# MCU.net
KiCad netlist of a schematic drawn in Altium Designer
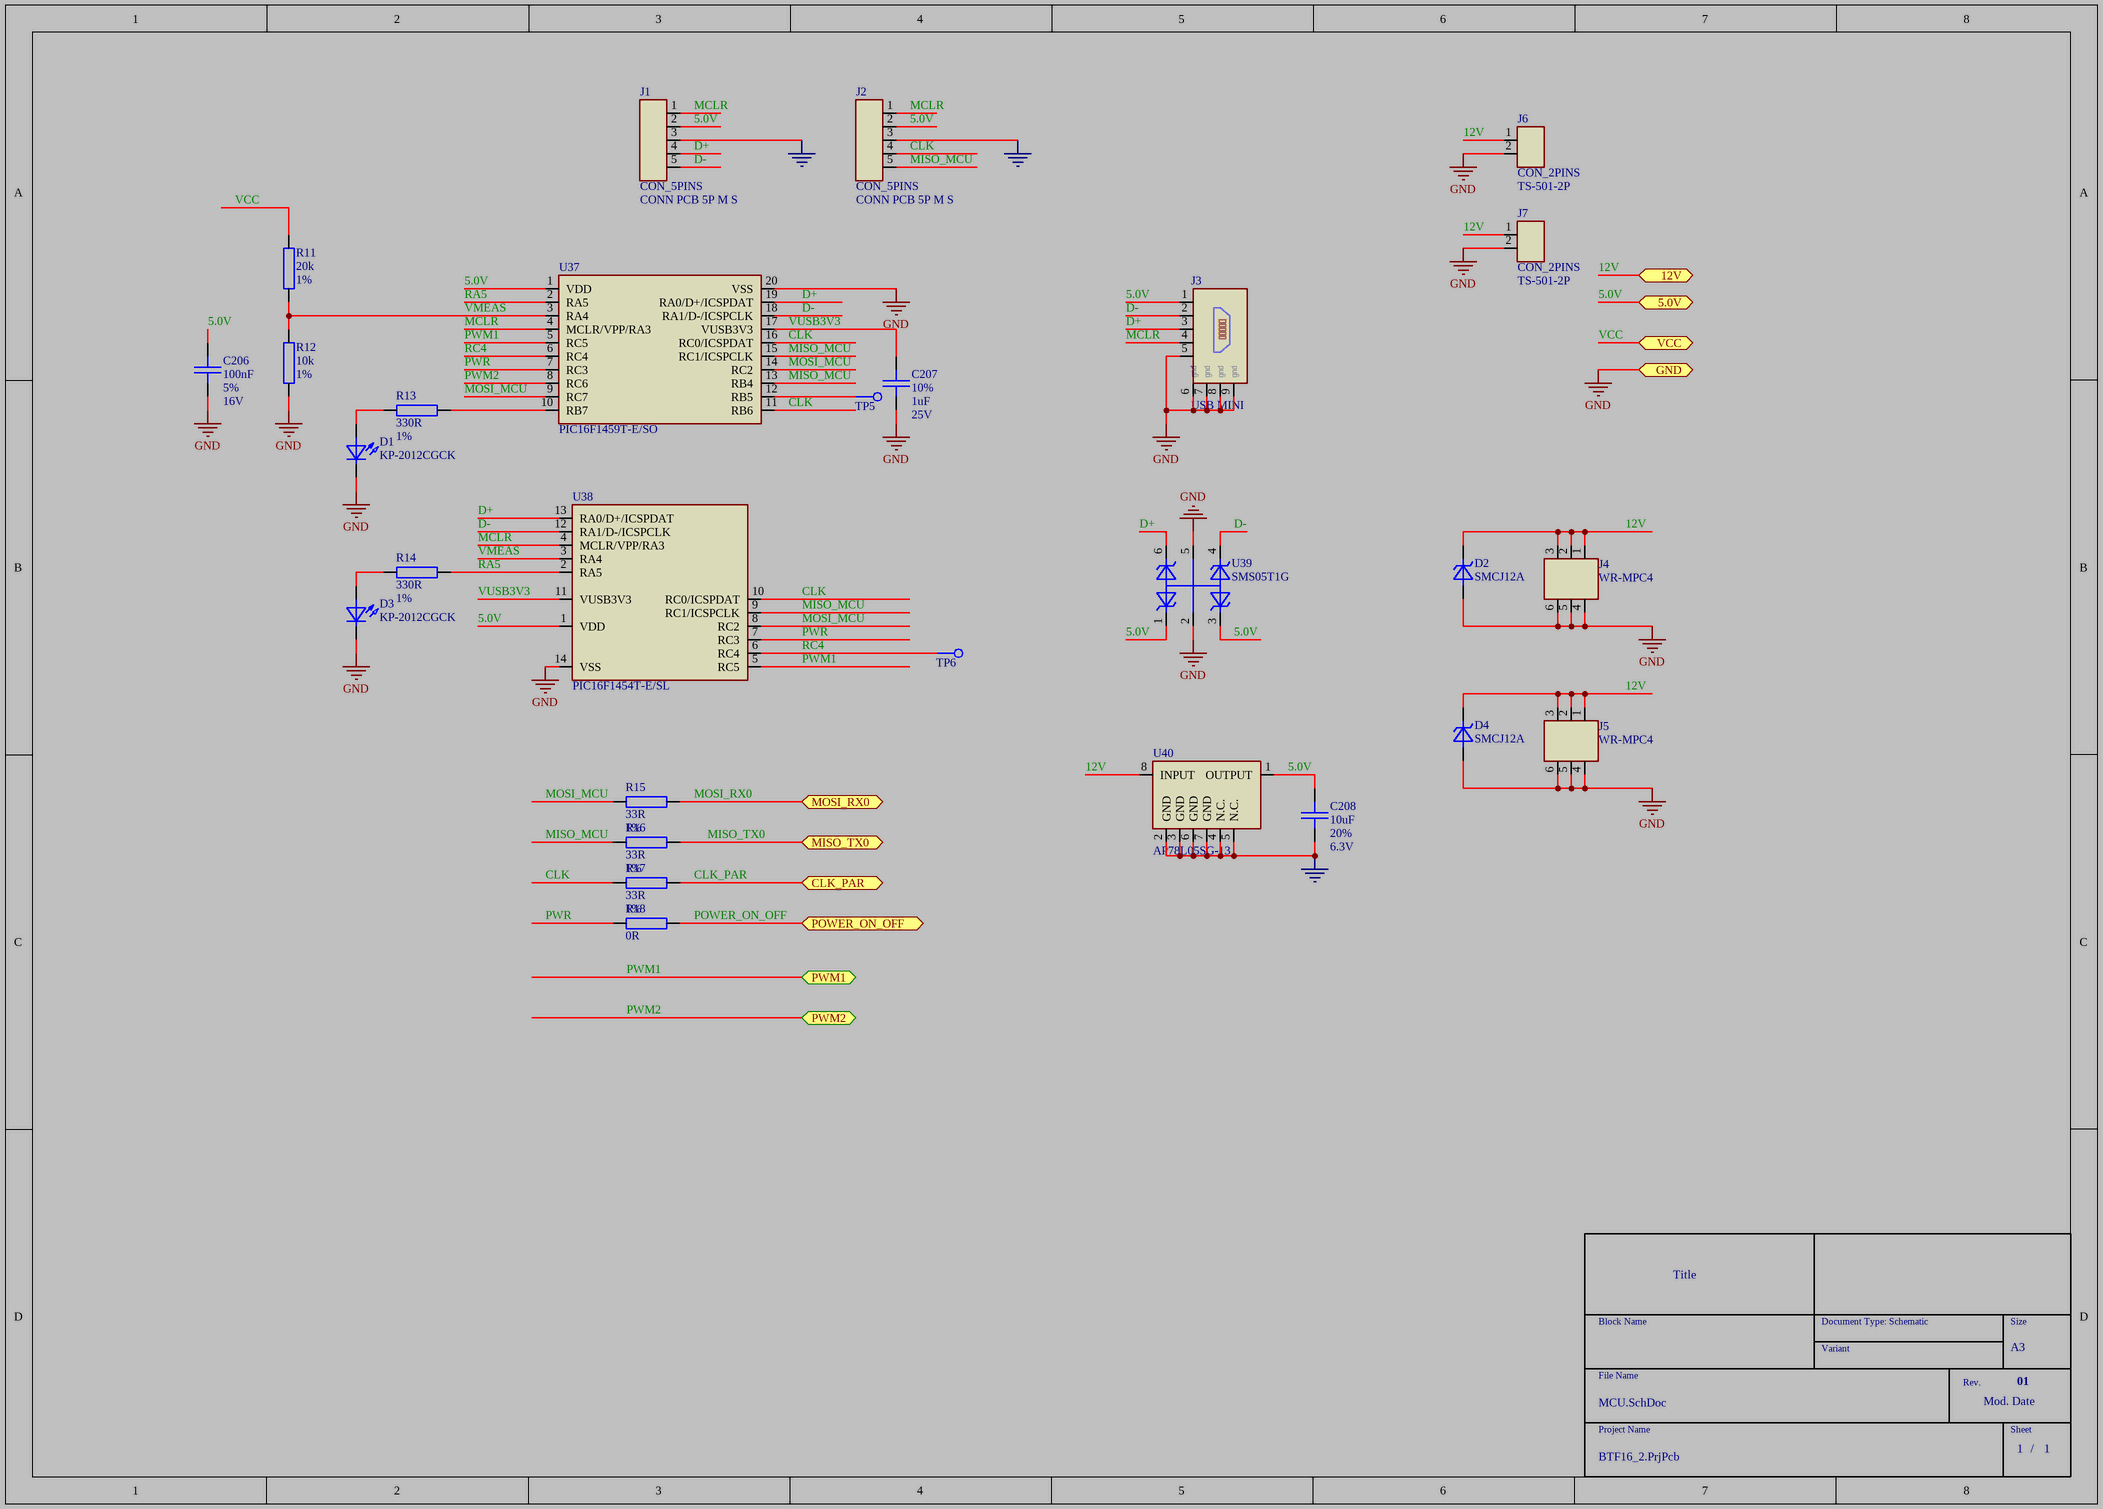
[diagram p0: MCU.SchDoc]

(export (version "E")
  (design (tool "Eeschema 10.0.6"))
  (components
    (comp (ref "C206")
      (value "C")
      (footprint "SMD_0603_CAPC1608X95N")
      (fields
        (field (name "DB_PART_NUMBER") "CAP000027134")
        (field (name "DB_VALUE") "100nF")
        (field (name "DB_TOLERANCE") "5%")
        (field (name "DB_VOLTAGE") "16V")
        (field (name "DB_MANUFACTURER_PART") "KEMET    C0603C104J4RAC")
      )
      (libsource (lib "Database_Libs1") (part "C"))
    )
    (comp (ref "C207")
      (value "C")
      (footprint "SMD_0603_CAPC1608X80N")
      (fields
        (field (name "DB_MANUFACTURER_PART") "TDK      CGA3E1X7R1E105KT")
        (field (name "DB_PART_NUMBER") "CAP000047176")
        (field (name "DB_TOLERANCE") "10%")
        (field (name "DB_VALUE") "1uF")
        (field (name "DB_VOLTAGE") "25V")
        (field (name "DB_APPROVED_BY") "VSN")
      )
      (libsource (lib "Database_Libs1") (part "C"))
    )
    (comp (ref "C208")
      (value "C")
      (footprint "SMD_0603_CAPC1608X95N")
      (fields
        (field (name "DB_PART_NUMBER") "CAP000043646")
        (field (name "DB_VALUE") "10uF")
        (field (name "DB_TOLERANCE") "20%")
        (field (name "DB_VOLTAGE") "6.3V")
        (field (name "DB_MANUFACTURER_PART") "KEMET    C0603C106M9PAC")
      )
      (libsource (lib "Database_Libs1") (part "C"))
    )
    (comp (ref "D1")
      (value "LED")
      (footprint "SMD_LED2012X100N")
      (fields
        (field (name "DB_PART_NUMBER") "OPT000000096")
        (field (name "DB_VALUE") "KP-2012CGCK")
        (field (name "DB_MANUFACTURER_PART") "KINGBRIGHT       KP-2012CGCK")
        (field (name "DB_APPROVED_BY") "VSN")
      )
      (libsource (lib "Database_Libs1") (part "LED"))
    )
    (comp (ref "D2")
      (value "D_TVS_UNI")
      (footprint "SMD_DO214AC_SMC")
      (fields
        (field (name "DB_PART_NUMBER") "DDE000001725")
        (field (name "DB_VALUE") "SMCJ12A")
        (field (name "DB_MANUFACTURER_PART") "Diodes        SMCJ12A")
      )
      (libsource (lib "Database_Libs1") (part "D_TVS_UNI"))
    )
    (comp (ref "D3")
      (value "LED")
      (footprint "SMD_LED2012X100N")
      (fields
        (field (name "DB_PART_NUMBER") "OPT000000096")
        (field (name "DB_VALUE") "KP-2012CGCK")
        (field (name "DB_MANUFACTURER_PART") "KINGBRIGHT       KP-2012CGCK")
        (field (name "DB_APPROVED_BY") "VSN")
      )
      (libsource (lib "Database_Libs1") (part "LED"))
    )
    (comp (ref "D4")
      (value "D_TVS_UNI")
      (footprint "SMD_DO214AC_SMC")
      (fields
        (field (name "DB_PART_NUMBER") "DDE000001725")
        (field (name "DB_VALUE") "SMCJ12A")
        (field (name "DB_MANUFACTURER_PART") "Diodes        SMCJ12A")
      )
      (libsource (lib "Database_Libs1") (part "D_TVS_UNI"))
    )
    (comp (ref "J1")
      (value "CON_5PINS")
      (footprint "PTH_HDRV05W64P254_1X05")
      (fields
        (field (name "DB_PART_NUMBER") "CON000000006")
        (field (name "DB_VALUE") "CONN PCB 5P M S")
        (field (name "DB_MANUFACTURER_PART") "W+P        143-12-005-00")
        (field (name "DB_APPROVED_BY") "VSN")
      )
      (libsource (lib "Database_Libs1") (part "CON_5PINS"))
    )
    (comp (ref "J2")
      (value "CON_5PINS")
      (footprint "PTH_HDRV05W64P254_1X05")
      (fields
        (field (name "DB_PART_NUMBER") "CON000000006")
        (field (name "DB_VALUE") "CONN PCB 5P M S")
        (field (name "DB_MANUFACTURER_PART") "W+P        143-12-005-00")
        (field (name "DB_APPROVED_BY") "VSN")
      )
      (libsource (lib "Database_Libs1") (part "CON_5PINS"))
    )
    (comp (ref "J3")
      (value "CON_USB_MINI_1")
      (footprint "SMD_CON-CVILUX-CU04-SCM15B0")
      (fields
        (field (name "DB_PART_NUMBER") "CON000000048")
        (field (name "DB_VALUE") "USB MINI")
        (field (name "DB_MANUFACTURER_PART") "CVILUX       CU04-SCM15B0-R0-LF")
        (field (name "DB_APPROVED_BY") "VSN")
      )
      (libsource (lib "Database_Libs1") (part "CON_USB_MINI_1"))
    )
    (comp (ref "J4")
      (value "CON_2ROWS_6PINS_1")
      (footprint "PTH_CON_WR-MRC4-6P_S")
      (fields
        (field (name "DB_PART_NUMBER") "CON000000279")
        (field (name "DB_VALUE") "WR-MPC4")
        (field (name "DB_MANUFACTURER_PART") "WE        	649 006 211 22")
        (field (name "DB_APPROVED_BY") "VSN")
      )
      (libsource (lib "Database_Libs1") (part "CON_2ROWS_6PINS_1"))
    )
    (comp (ref "J5")
      (value "CON_2ROWS_6PINS_1")
      (footprint "PTH_CON_WR-MRC4-6P_S")
      (fields
        (field (name "DB_PART_NUMBER") "CON000000279")
        (field (name "DB_VALUE") "WR-MPC4")
        (field (name "DB_MANUFACTURER_PART") "WE        	649 006 211 22")
        (field (name "DB_APPROVED_BY") "VSN")
      )
      (libsource (lib "Database_Libs1") (part "CON_2ROWS_6PINS_1"))
    )
    (comp (ref "J6")
      (value "CON_2PINS")
      (footprint "PTH_HDRV02W11060P500_1X02")
      (fields
        (field (name "DB_PART_NUMBER") "CON000000055")
        (field (name "DB_VALUE") "TS-501-2P")
        (field (name "DB_MANUFACTURER_PART") "HOW DER      TS-501-2P")
        (field (name "DB_APPROVED_BY") "VSN")
      )
      (libsource (lib "Database_Libs1") (part "CON_2PINS"))
    )
    (comp (ref "J7")
      (value "CON_2PINS")
      (footprint "PTH_HDRV02W11060P500_1X02")
      (fields
        (field (name "DB_PART_NUMBER") "CON000000055")
        (field (name "DB_VALUE") "TS-501-2P")
        (field (name "DB_MANUFACTURER_PART") "HOW DER      TS-501-2P")
        (field (name "DB_APPROVED_BY") "VSN")
      )
      (libsource (lib "Database_Libs1") (part "CON_2PINS"))
    )
    (comp (ref "R11")
      (value "R")
      (footprint "SMD_0603_RESC1608X55N")
      (fields
        (field (name "DB_PART_NUMBER") "RES000006283")
        (field (name "DB_VALUE") "20k")
        (field (name "DB_TOLERANCE") "1%")
        (field (name "DB_MANUFACTURER_PART") "YAGEO    RC0603FR-0720K")
      )
      (libsource (lib "Database_Libs1") (part "R"))
    )
    (comp (ref "R12")
      (value "R")
      (footprint "SMD_0603_RESC1608X55N")
      (fields
        (field (name "DB_PART_NUMBER") "RES000008891")
        (field (name "DB_VALUE") "10k")
        (field (name "DB_TOLERANCE") "1%")
        (field (name "DB_MANUFACTURER_PART") "VISHAY    CRCW060310K0FKEA")
        (field (name "DB_APPROVED_BY") "VSN")
      )
      (libsource (lib "Database_Libs1") (part "R"))
    )
    (comp (ref "R13")
      (value "R")
      (footprint "SMD_0603_RESC1608X55N")
      (fields
        (field (name "DB_PART_NUMBER") "RES000006240")
        (field (name "DB_VALUE") "330R")
        (field (name "DB_TOLERANCE") "1%")
        (field (name "DB_MANUFACTURER_PART") "YAGEO    RC0603FR-07330R")
      )
      (libsource (lib "Database_Libs1") (part "R"))
    )
    (comp (ref "R14")
      (value "R")
      (footprint "SMD_0603_RESC1608X55N")
      (fields
        (field (name "DB_PART_NUMBER") "RES000006240")
        (field (name "DB_VALUE") "330R")
        (field (name "DB_TOLERANCE") "1%")
        (field (name "DB_MANUFACTURER_PART") "YAGEO    RC0603FR-07330R")
      )
      (libsource (lib "Database_Libs1") (part "R"))
    )
    (comp (ref "R15")
      (value "R")
      (footprint "SMD_0201_RESC0603X26N")
      (fields
        (field (name "DB_PART_NUMBER") "RES000005550")
        (field (name "DB_VALUE") "33R")
        (field (name "DB_TOLERANCE") "1%")
        (field (name "DB_MANUFACTURER_PART") "YAGEO    RC0201FR-0733R")
      )
      (libsource (lib "Database_Libs1") (part "R"))
    )
    (comp (ref "R16")
      (value "R")
      (footprint "SMD_0201_RESC0603X26N")
      (fields
        (field (name "DB_PART_NUMBER") "RES000005550")
        (field (name "DB_VALUE") "33R")
        (field (name "DB_TOLERANCE") "1%")
        (field (name "DB_MANUFACTURER_PART") "YAGEO    RC0201FR-0733R")
      )
      (libsource (lib "Database_Libs1") (part "R"))
    )
    (comp (ref "R17")
      (value "R")
      (footprint "SMD_0201_RESC0603X26N")
      (fields
        (field (name "DB_PART_NUMBER") "RES000005550")
        (field (name "DB_VALUE") "33R")
        (field (name "DB_TOLERANCE") "1%")
        (field (name "DB_MANUFACTURER_PART") "YAGEO    RC0201FR-0733R")
      )
      (libsource (lib "Database_Libs1") (part "R"))
    )
    (comp (ref "R18")
      (value "R")
      (footprint "SMD_0603_RESC1608X55N")
      (fields
        (field (name "DB_PART_NUMBER") "RES000008926")
        (field (name "DB_VALUE") "0R")
        (field (name "DB_MANUFACTURER_PART") "YAGEO    AC0603FR-070RL")
        (field (name "DB_APPROVED_BY") "VSN")
      )
      (libsource (lib "Database_Libs1") (part "R"))
    )
    (comp (ref "TP5")
      (value "TEST_POINT_1")
      (footprint "SMD_TP_100-254")
      (fields (field (name "DB_PART_NUMBER") "TPO000000001"))
      (libsource (lib "Database_Libs1") (part "TEST_POINT_1"))
    )
    (comp (ref "TP6")
      (value "TEST_POINT_1")
      (footprint "SMD_TP_100-254")
      (fields (field (name "DB_PART_NUMBER") "TPO000000001"))
      (libsource (lib "Database_Libs1") (part "TEST_POINT_1"))
    )
    (comp (ref "U37")
      (value "IC_PIC16F1459")
      (footprint "SMD_SOIC127P1030X265-20N")
      (fields
        (field (name "DB_PART_NUMBER") "MCU000000108")
        (field (name "DB_VALUE") "PIC16F1459T-E/SO")
        (field (name "DB_MANUFACTURER_PART") "MICROCHIP        PIC16F1459T-E/SO")
        (field (name "DB_APPROVED_BY") "VSN")
      )
      (libsource (lib "Database_Libs1") (part "IC_PIC16F1459"))
    )
    (comp (ref "U38")
      (value "IC_PIC16F1454TESL-SO14")
      (footprint "SMD_SOIC127P600X175-14N")
      (fields
        (field (name "DB_PART_NUMBER") "MCU000000093")
        (field (name "DB_VALUE") "PIC16F1454T-E/SL")
        (field (name "DB_MANUFACTURER_PART") "MICROCHIP       PIC16F1454T-E/SL")
        (field (name "DB_APPROVED_BY") "VSN")
      )
      (libsource (lib "Database_Libs1") (part "IC_PIC16F1454TESL-SO14"))
    )
    (comp (ref "U39")
      (value "D_TVS_QUAD_C1A2C3C4A5C6")
      (footprint "SMD_SOT457_SOT95P275X110-6N")
      (fields
        (field (name "DB_PART_NUMBER") "DDE000002846")
        (field (name "DB_VALUE") "SMS05T1G")
        (field (name "DB_MANUFACTURER_PART") "ON SEMICONDUCTOR        SMS05T1G")
        (field (name "DB_APPROVED_BY") "VSN")
      )
      (libsource (lib "Database_Libs1") (part "D_TVS_QUAD_C1A2C3C4A5C6"))
    )
    (comp (ref "U40")
      (value "IC_LM2931AD-5.0R2G_SO-8")
      (footprint "SMD_SOIC127P600X175-8N")
      (fields
        (field (name "DB_PART_NUMBER") "PSU000000125")
        (field (name "DB_VALUE") "AP78L05SG-13")
        (field (name "DB_MANUFACTURER_PART") "DIODES        AP78L05SG-13")
        (field (name "DB_APPROVED_BY") "VSN")
      )
      (libsource (lib "Database_Libs1") (part "IC_LM2931AD-5.0R2G_SO-8"))
    )
  )
  (nets
    (net (code "1") (name "/5.0V") (class "Default")
      (node (ref "C206") (pin "1") (pinfunction "1_1") (pintype "passive"))
      (node (ref "C208") (pin "1") (pinfunction "1_1") (pintype "passive"))
      (node (ref "J1") (pin "2") (pinfunction "2_2") (pintype "passive"))
      (node (ref "J2") (pin "2") (pinfunction "2_2") (pintype "passive"))
      (node (ref "J3") (pin "1") (pinfunction "1_1") (pintype "passive"))
      (node (ref "U37") (pin "1") (pinfunction "VDD_1") (pintype "passive"))
      (node (ref "U38") (pin "1") (pinfunction "VDD_1") (pintype "passive"))
      (node (ref "U39") (pin "1") (pinfunction "1_1") (pintype "passive"))
      (node (ref "U39") (pin "3") (pinfunction "3_3") (pintype "passive"))
      (node (ref "U40") (pin "1") (pinfunction "OUTPUT_1") (pintype "passive"))
    )
    (net (code "2") (name "/12V") (class "Default")
      (node (ref "D2") (pin "1") (pinfunction "C_1") (pintype "passive"))
      (node (ref "D4") (pin "1") (pinfunction "C_1") (pintype "passive"))
      (node (ref "J4") (pin "1") (pinfunction "1_1") (pintype "passive"))
      (node (ref "J4") (pin "2") (pinfunction "2_2") (pintype "passive"))
      (node (ref "J4") (pin "3") (pinfunction "3_3") (pintype "passive"))
      (node (ref "J5") (pin "1") (pinfunction "1_1") (pintype "passive"))
      (node (ref "J5") (pin "2") (pinfunction "2_2") (pintype "passive"))
      (node (ref "J5") (pin "3") (pinfunction "3_3") (pintype "passive"))
      (node (ref "J6") (pin "1") (pinfunction "1_1") (pintype "passive"))
      (node (ref "J7") (pin "1") (pinfunction "1_1") (pintype "passive"))
      (node (ref "U40") (pin "8") (pinfunction "INPUT_8") (pintype "passive"))
    )
    (net (code "3") (name "/CLK") (class "Default")
      (node (ref "J2") (pin "4") (pinfunction "4_4") (pintype "passive"))
      (node (ref "R17") (pin "1") (pinfunction "1_1") (pintype "passive"))
      (node (ref "U37") (pin "11") (pinfunction "RB6_11") (pintype "passive"))
      (node (ref "U37") (pin "16") (pinfunction "RC0/ICSPDAT_16") (pintype "passive"))
      (node (ref "U38") (pin "10") (pinfunction "RC0/ICSPDAT_10") (pintype "passive"))
    )
    (net (code "4") (name "/CLK_PAR") (class "Default")
      (node (ref "R17") (pin "2") (pinfunction "2_2") (pintype "passive"))
    )
    (net (code "5") (name "/D+") (class "Default")
      (node (ref "J1") (pin "4") (pinfunction "4_4") (pintype "passive"))
      (node (ref "J3") (pin "3") (pinfunction "3_3") (pintype "passive"))
      (node (ref "U37") (pin "19") (pinfunction "RA0/D+/ICSPDAT_19") (pintype "passive"))
      (node (ref "U38") (pin "13") (pinfunction "RA0/D+/ICSPDAT_13") (pintype "passive"))
      (node (ref "U39") (pin "6") (pinfunction "6_6") (pintype "passive"))
    )
    (net (code "6") (name "/D-") (class "Default")
      (node (ref "J1") (pin "5") (pinfunction "5_5") (pintype "passive"))
      (node (ref "J3") (pin "2") (pinfunction "2_2") (pintype "passive"))
      (node (ref "U37") (pin "18") (pinfunction "RA1/D-/ICSPCLK_18") (pintype "passive"))
      (node (ref "U38") (pin "12") (pinfunction "RA1/D-/ICSPCLK_12") (pintype "passive"))
      (node (ref "U39") (pin "4") (pinfunction "4_4") (pintype "passive"))
    )
    (net (code "7") (name "/MCLR") (class "Default")
      (node (ref "J1") (pin "1") (pinfunction "1_1") (pintype "passive"))
      (node (ref "J2") (pin "1") (pinfunction "1_1") (pintype "passive"))
      (node (ref "J3") (pin "4") (pinfunction "4_4") (pintype "passive"))
      (node (ref "U37") (pin "4") (pinfunction "MCLR/VPP/RA3_4") (pintype "passive"))
      (node (ref "U38") (pin "4") (pinfunction "MCLR/VPP/RA3_4") (pintype "passive"))
    )
    (net (code "8") (name "/MISO_MCU") (class "Default")
      (node (ref "J2") (pin "5") (pinfunction "5_5") (pintype "passive"))
      (node (ref "R16") (pin "1") (pinfunction "1_1") (pintype "passive"))
      (node (ref "U37") (pin "13") (pinfunction "RB4_13") (pintype "passive"))
      (node (ref "U37") (pin "15") (pinfunction "RC1/ICSPCLK_15") (pintype "passive"))
      (node (ref "U38") (pin "9") (pinfunction "RC1/ICSPCLK_9") (pintype "passive"))
    )
    (net (code "9") (name "/MISO_TX0") (class "Default")
      (node (ref "R16") (pin "2") (pinfunction "2_2") (pintype "passive"))
    )
    (net (code "10") (name "/MOSI_MCU") (class "Default")
      (node (ref "R15") (pin "1") (pinfunction "1_1") (pintype "passive"))
      (node (ref "U37") (pin "14") (pinfunction "RC2_14") (pintype "passive"))
      (node (ref "U37") (pin "9") (pinfunction "RC7_9") (pintype "passive"))
      (node (ref "U38") (pin "8") (pinfunction "RC2_8") (pintype "passive"))
    )
    (net (code "11") (name "/MOSI_RX0") (class "Default")
      (node (ref "R15") (pin "2") (pinfunction "2_2") (pintype "passive"))
    )
    (net (code "12") (name "/POWER_ON_OFF") (class "Default")
      (node (ref "R18") (pin "2") (pinfunction "2_2") (pintype "passive"))
    )
    (net (code "13") (name "/PWM1") (class "Default")
      (node (ref "U37") (pin "5") (pinfunction "RC5_5") (pintype "passive"))
      (node (ref "U38") (pin "5") (pinfunction "RC5_5") (pintype "passive"))
    )
    (net (code "14") (name "/PWM2") (class "Default")
      (node (ref "U37") (pin "8") (pinfunction "RC6_8") (pintype "passive"))
    )
    (net (code "15") (name "/PWR") (class "Default")
      (node (ref "R18") (pin "1") (pinfunction "1_1") (pintype "passive"))
      (node (ref "U37") (pin "7") (pinfunction "RC3_7") (pintype "passive"))
      (node (ref "U38") (pin "7") (pinfunction "RC3_7") (pintype "passive"))
    )
    (net (code "16") (name "/RA5") (class "Default")
      (node (ref "R14") (pin "2") (pinfunction "2_2") (pintype "passive"))
      (node (ref "U37") (pin "2") (pinfunction "RA5_2") (pintype "passive"))
      (node (ref "U38") (pin "2") (pinfunction "RA5_2") (pintype "passive"))
    )
    (net (code "17") (name "/RC4") (class "Default")
      (node (ref "TP6") (pin "1") (pinfunction "1_1") (pintype "passive"))
      (node (ref "U37") (pin "6") (pinfunction "RC4_6") (pintype "passive"))
      (node (ref "U38") (pin "6") (pinfunction "RC4_6") (pintype "passive"))
    )
    (net (code "18") (name "/VCC") (class "Default")
      (node (ref "R11") (pin "1") (pinfunction "1_1") (pintype "passive"))
    )
    (net (code "19") (name "/VMEAS") (class "Default")
      (node (ref "R11") (pin "2") (pinfunction "2_2") (pintype "passive"))
      (node (ref "R12") (pin "1") (pinfunction "1_1") (pintype "passive"))
      (node (ref "U37") (pin "3") (pinfunction "RA4_3") (pintype "passive"))
      (node (ref "U38") (pin "3") (pinfunction "RA4_3") (pintype "passive"))
    )
    (net (code "20") (name "/VUSB3V3") (class "Default")
      (node (ref "C207") (pin "1") (pinfunction "1_1") (pintype "passive"))
      (node (ref "U37") (pin "17") (pinfunction "VUSB3V3_17") (pintype "passive"))
      (node (ref "U38") (pin "11") (pinfunction "VUSB3V3_11") (pintype "passive"))
    )
    (net (code "21") (name "GND") (class "Default")
      (node (ref "C206") (pin "2") (pinfunction "2_2") (pintype "passive"))
      (node (ref "C207") (pin "2") (pinfunction "2_2") (pintype "passive"))
      (node (ref "C208") (pin "2") (pinfunction "2_2") (pintype "passive"))
      (node (ref "D1") (pin "1") (pinfunction "C_1") (pintype "passive"))
      (node (ref "D2") (pin "2") (pinfunction "A_2") (pintype "passive"))
      (node (ref "D3") (pin "1") (pinfunction "C_1") (pintype "passive"))
      (node (ref "D4") (pin "2") (pinfunction "A_2") (pintype "passive"))
      (node (ref "J1") (pin "3") (pinfunction "3_3") (pintype "passive"))
      (node (ref "J2") (pin "3") (pinfunction "3_3") (pintype "passive"))
      (node (ref "J3") (pin "5") (pinfunction "5_5") (pintype "passive"))
      (node (ref "J3") (pin "6") (pinfunction "6_6") (pintype "passive"))
      (node (ref "J3") (pin "7") (pinfunction "7_7") (pintype "passive"))
      (node (ref "J3") (pin "8") (pinfunction "8_8") (pintype "passive"))
      (node (ref "J3") (pin "9") (pinfunction "9_9") (pintype "passive"))
      (node (ref "J4") (pin "4") (pinfunction "4_4") (pintype "passive"))
      (node (ref "J4") (pin "5") (pinfunction "5_5") (pintype "passive"))
      (node (ref "J4") (pin "6") (pinfunction "6_6") (pintype "passive"))
      (node (ref "J5") (pin "4") (pinfunction "4_4") (pintype "passive"))
      (node (ref "J5") (pin "5") (pinfunction "5_5") (pintype "passive"))
      (node (ref "J5") (pin "6") (pinfunction "6_6") (pintype "passive"))
      (node (ref "J6") (pin "2") (pinfunction "2_2") (pintype "passive"))
      (node (ref "J7") (pin "2") (pinfunction "2_2") (pintype "passive"))
      (node (ref "R12") (pin "2") (pinfunction "2_2") (pintype "passive"))
      (node (ref "U37") (pin "20") (pinfunction "VSS_20") (pintype "passive"))
      (node (ref "U38") (pin "14") (pinfunction "VSS_14") (pintype "passive"))
      (node (ref "U39") (pin "2") (pinfunction "2_2") (pintype "passive"))
      (node (ref "U39") (pin "5") (pinfunction "5_5") (pintype "passive"))
      (node (ref "U40") (pin "2") (pinfunction "GND_2") (pintype "passive"))
      (node (ref "U40") (pin "3") (pinfunction "GND_3") (pintype "passive"))
      (node (ref "U40") (pin "4") (pinfunction "N.C._4") (pintype "passive"))
      (node (ref "U40") (pin "5") (pinfunction "N.C._5") (pintype "passive"))
      (node (ref "U40") (pin "6") (pinfunction "GND_6") (pintype "passive"))
      (node (ref "U40") (pin "7") (pinfunction "GND_7") (pintype "passive"))
    )
    (net (code "22") (name "Net-(D1-A)") (class "Default")
      (node (ref "D1") (pin "2") (pinfunction "A_2") (pintype "passive"))
      (node (ref "R13") (pin "1") (pinfunction "1_1") (pintype "passive"))
    )
    (net (code "23") (name "Net-(D3-A)") (class "Default")
      (node (ref "D3") (pin "2") (pinfunction "A_2") (pintype "passive"))
      (node (ref "R14") (pin "1") (pinfunction "1_1") (pintype "passive"))
    )
    (net (code "24") (name "Net-(U37-RB5)") (class "Default")
      (node (ref "TP5") (pin "1") (pinfunction "1_1") (pintype "passive"))
      (node (ref "U37") (pin "12") (pinfunction "RB5_12") (pintype "passive"))
    )
    (net (code "25") (name "Net-(U37-RB7)") (class "Default")
      (node (ref "R13") (pin "2") (pinfunction "2_2") (pintype "passive"))
      (node (ref "U37") (pin "10") (pinfunction "RB7_10") (pintype "passive"))
    )
  )
)
